# hm3.net
KiCad netlist of a schematic drawn in EAGLE
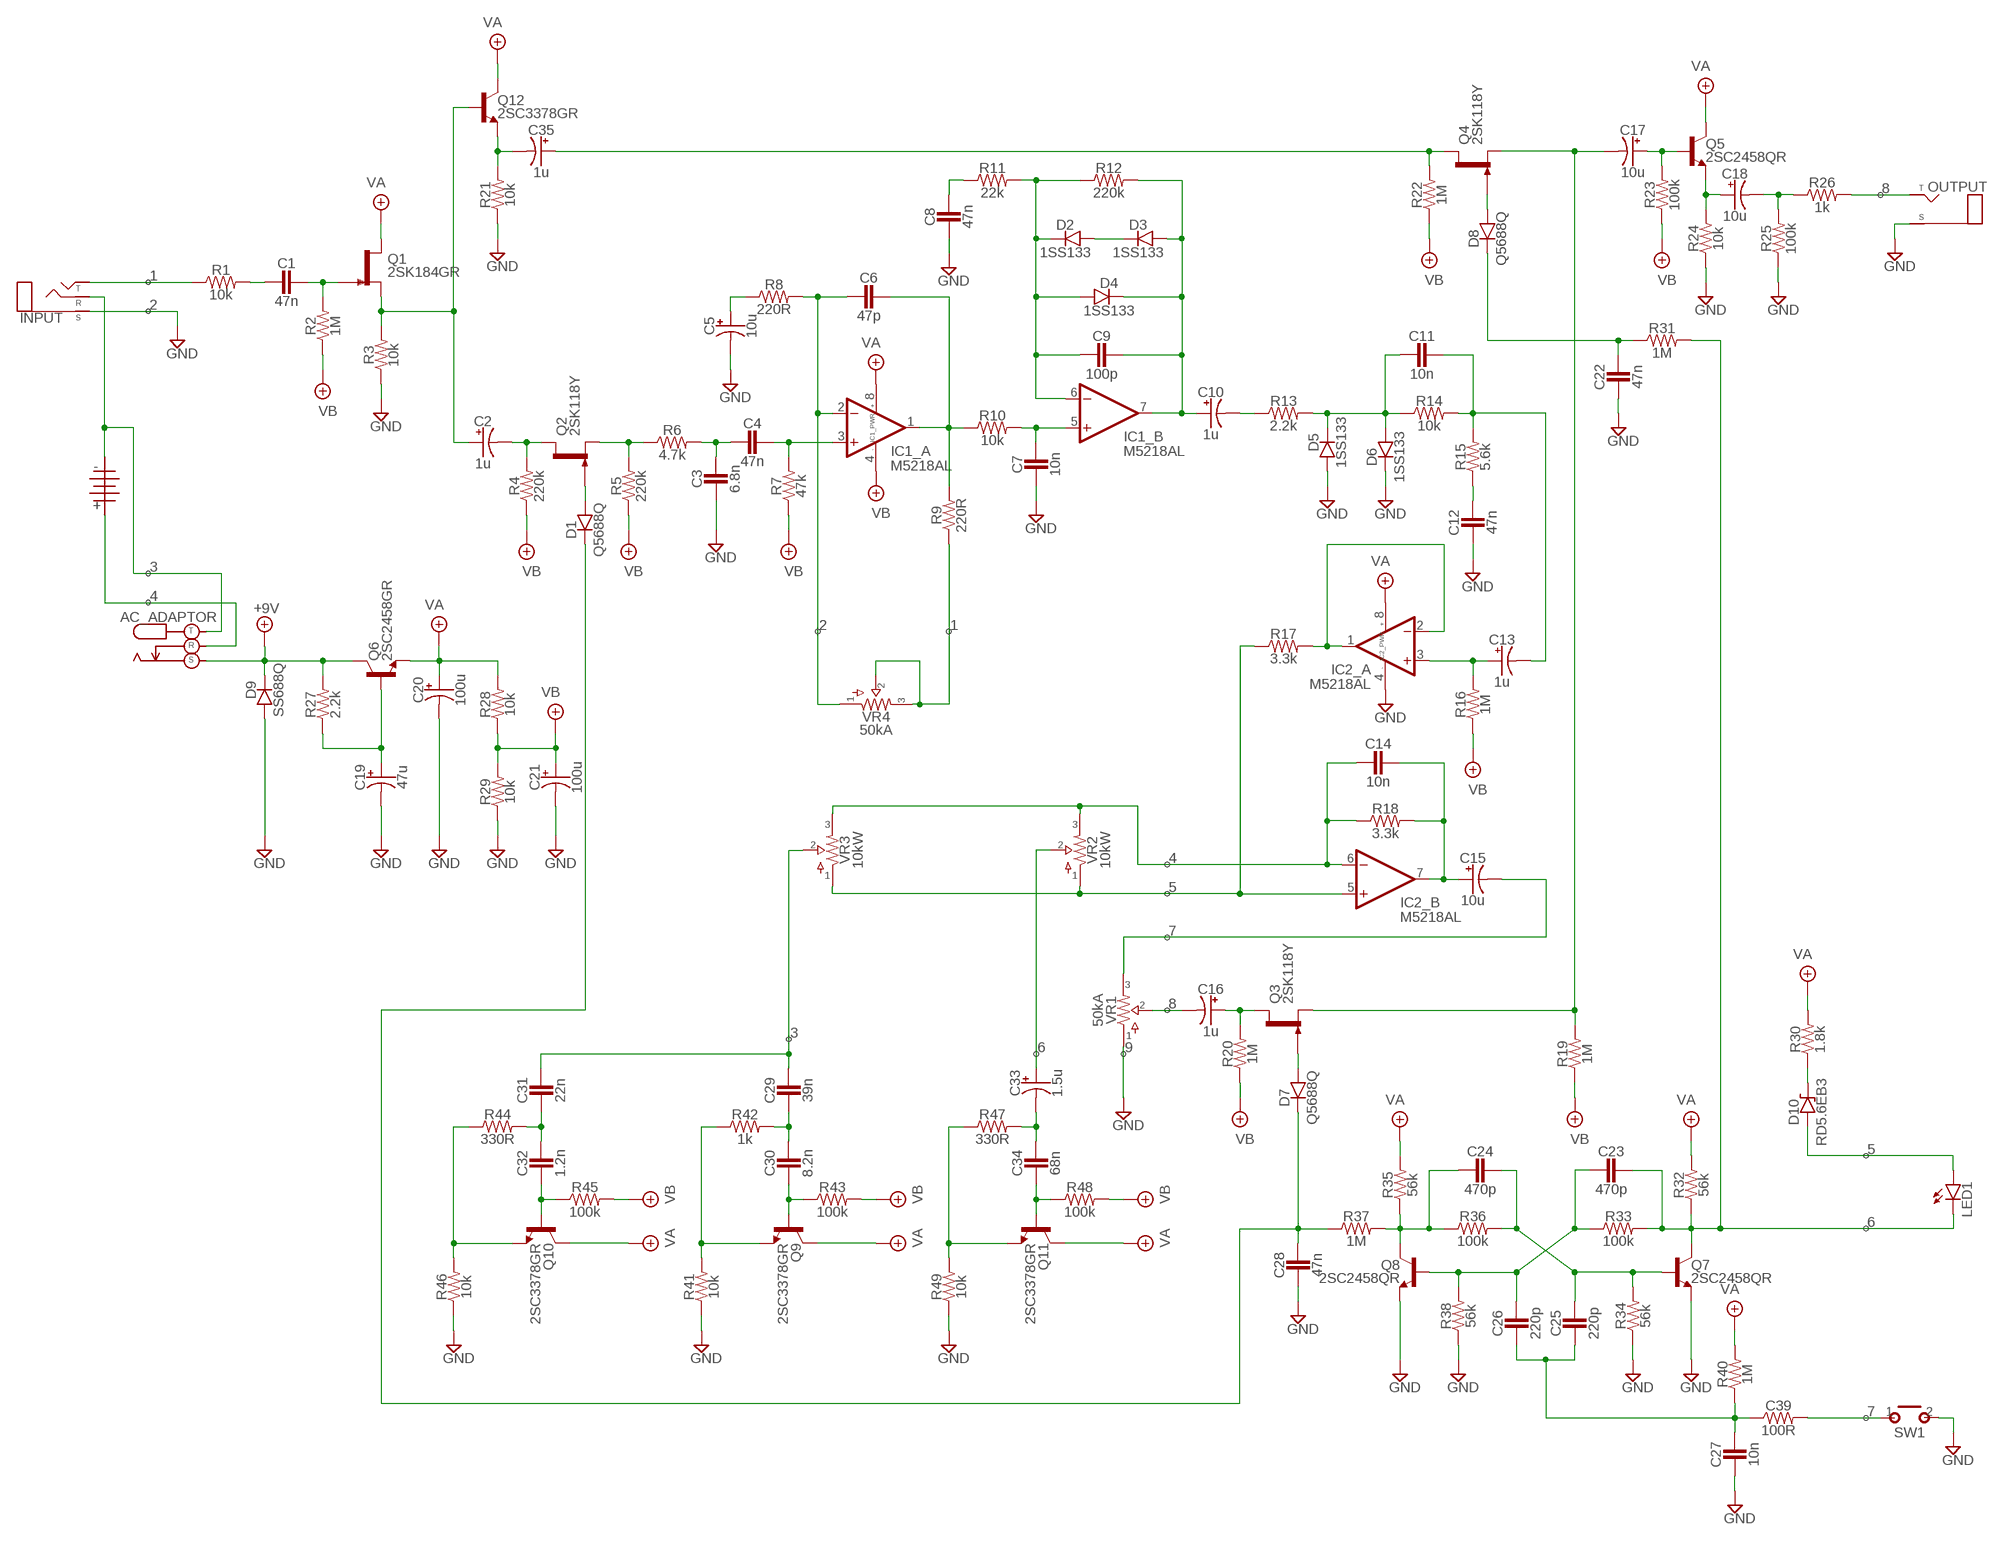
[diagram p0: schematic, sheet 1]

(export (version "E")
  (design (tool "Eeschema 10.0.6"))
  (components
    (comp (ref "1101")
      (value "BATTERY")
      (footprint "eagle-import:TWO_PADS")
      (libsource (lib "eagle-import") (part "BATTERY"))
    )
    (comp (ref "AC_ADAPTOR")
      (value "DC_KOBICONN")
      (footprint "eagle-import:DC_KOBICONN")
      (libsource (lib "eagle-import") (part "DC_KOBICONN"))
    )
    (comp (ref "C1")
      (value "47n")
      (footprint "eagle-import:BOX_SMALL")
      (libsource (lib "eagle-import") (part "CER/FILMBOX.1"))
    )
    (comp (ref "C2")
      (value "1u")
      (footprint "eagle-import:050_020")
      (libsource (lib "eagle-import") (part "0500"))
    )
    (comp (ref "C3")
      (value "6.8n")
      (footprint "eagle-import:BOX_SMALL")
      (libsource (lib "eagle-import") (part "CER/FILMBOX.1"))
    )
    (comp (ref "C4")
      (value "47n")
      (footprint "eagle-import:BOX_SMALL")
      (libsource (lib "eagle-import") (part "CER/FILMBOX.1"))
    )
    (comp (ref "C5")
      (value "10u")
      (footprint "eagle-import:050_020")
      (libsource (lib "eagle-import") (part "0500"))
    )
    (comp (ref "C6")
      (value "47p")
      (footprint "eagle-import:BOX_SMALL")
      (libsource (lib "eagle-import") (part "CER/FILMBOX.1"))
    )
    (comp (ref "C7")
      (value "10n")
      (footprint "eagle-import:BOX_SMALL")
      (libsource (lib "eagle-import") (part "CER/FILMBOX.1"))
    )
    (comp (ref "C8")
      (value "47n")
      (footprint "eagle-import:BOX_SMALL")
      (libsource (lib "eagle-import") (part "CER/FILMBOX.1"))
    )
    (comp (ref "C9")
      (value "100p")
      (footprint "eagle-import:BOX_SMALL")
      (libsource (lib "eagle-import") (part "CER/FILMBOX.1"))
    )
    (comp (ref "C10")
      (value "1u")
      (footprint "eagle-import:050_020")
      (libsource (lib "eagle-import") (part "0500"))
    )
    (comp (ref "C11")
      (value "10n")
      (footprint "eagle-import:BOX_SMALL")
      (libsource (lib "eagle-import") (part "CER/FILMBOX.1"))
    )
    (comp (ref "C12")
      (value "47n")
      (footprint "eagle-import:BOX_SMALL")
      (libsource (lib "eagle-import") (part "CER/FILMBOX.1"))
    )
    (comp (ref "C13")
      (value "1u")
      (footprint "eagle-import:050_020")
      (libsource (lib "eagle-import") (part "0500"))
    )
    (comp (ref "C14")
      (value "10n")
      (footprint "eagle-import:BOX_SMALL")
      (libsource (lib "eagle-import") (part "CER/FILMBOX.1"))
    )
    (comp (ref "C15")
      (value "10u")
      (footprint "eagle-import:050_020")
      (libsource (lib "eagle-import") (part "0500"))
    )
    (comp (ref "C16")
      (value "1u")
      (footprint "eagle-import:050_020")
      (libsource (lib "eagle-import") (part "0500"))
    )
    (comp (ref "C17")
      (value "10u")
      (footprint "eagle-import:050_020")
      (libsource (lib "eagle-import") (part "0500"))
    )
    (comp (ref "C18")
      (value "10u")
      (footprint "eagle-import:050_020")
      (libsource (lib "eagle-import") (part "0500"))
    )
    (comp (ref "C19")
      (value "47u")
      (footprint "eagle-import:050_020")
      (libsource (lib "eagle-import") (part "0500"))
    )
    (comp (ref "C20")
      (value "100u")
      (footprint "eagle-import:050_020")
      (libsource (lib "eagle-import") (part "0500"))
    )
    (comp (ref "C21")
      (value "100u")
      (footprint "eagle-import:050_020")
      (libsource (lib "eagle-import") (part "0500"))
    )
    (comp (ref "C22")
      (value "47n")
      (footprint "eagle-import:BOX_SMALL")
      (libsource (lib "eagle-import") (part "CER/FILMBOX.1"))
    )
    (comp (ref "C23")
      (value "470p")
      (footprint "eagle-import:BOX_SMALL")
      (libsource (lib "eagle-import") (part "CER/FILMBOX.1"))
    )
    (comp (ref "C24")
      (value "470p")
      (footprint "eagle-import:BOX_SMALL")
      (libsource (lib "eagle-import") (part "CER/FILMBOX.1"))
    )
    (comp (ref "C25")
      (value "220p")
      (footprint "eagle-import:BOX_SMALL")
      (libsource (lib "eagle-import") (part "CER/FILMBOX.1"))
    )
    (comp (ref "C26")
      (value "220p")
      (footprint "eagle-import:BOX_SMALL")
      (libsource (lib "eagle-import") (part "CER/FILMBOX.1"))
    )
    (comp (ref "C27")
      (value "10n")
      (footprint "eagle-import:BOX_SMALL")
      (libsource (lib "eagle-import") (part "CER/FILMBOX.1"))
    )
    (comp (ref "C28")
      (value "47n")
      (footprint "eagle-import:BOX_SMALL")
      (libsource (lib "eagle-import") (part "CER/FILMBOX.1"))
    )
    (comp (ref "C29")
      (value "39n")
      (footprint "eagle-import:BOX_SMALL")
      (libsource (lib "eagle-import") (part "CER/FILMBOX.1"))
    )
    (comp (ref "C30")
      (value "8.2n")
      (footprint "eagle-import:BOX_SMALL")
      (libsource (lib "eagle-import") (part "CER/FILMBOX.1"))
    )
    (comp (ref "C31")
      (value "22n")
      (footprint "eagle-import:BOX_SMALL")
      (libsource (lib "eagle-import") (part "CER/FILMBOX.1"))
    )
    (comp (ref "C32")
      (value "1.2n")
      (footprint "eagle-import:BOX_SMALL")
      (libsource (lib "eagle-import") (part "CER/FILMBOX.1"))
    )
    (comp (ref "C33")
      (value "1.5u")
      (footprint "eagle-import:050_020")
      (libsource (lib "eagle-import") (part "0500"))
    )
    (comp (ref "C34")
      (value "68n")
      (footprint "eagle-import:BOX_SMALL")
      (libsource (lib "eagle-import") (part "CER/FILMBOX.1"))
    )
    (comp (ref "C35")
      (value "1u")
      (footprint "eagle-import:050_020")
      (libsource (lib "eagle-import") (part "0500"))
    )
    (comp (ref "C39")
      (value "100R")
      (footprint "eagle-import:R0207_3")
      (libsource (lib "eagle-import") (part "R_.3B"))
    )
    (comp (ref "D1")
      (value "Q5688Q")
      (footprint "eagle-import:DO35-2")
      (libsource (lib "eagle-import") (part "DO35.2"))
    )
    (comp (ref "D2")
      (value "1SS133")
      (footprint "eagle-import:DO35-2")
      (libsource (lib "eagle-import") (part "DO35.2"))
    )
    (comp (ref "D3")
      (value "1SS133")
      (footprint "eagle-import:DO35-2")
      (libsource (lib "eagle-import") (part "DO35.2"))
    )
    (comp (ref "D4")
      (value "1SS133")
      (footprint "eagle-import:DO35-2")
      (libsource (lib "eagle-import") (part "DO35.2"))
    )
    (comp (ref "D5")
      (value "1SS133")
      (footprint "eagle-import:DO35-2")
      (libsource (lib "eagle-import") (part "DO35.2"))
    )
    (comp (ref "D6")
      (value "1SS133")
      (footprint "eagle-import:DO35-2")
      (libsource (lib "eagle-import") (part "DO35.2"))
    )
    (comp (ref "D7")
      (value "Q5688Q")
      (footprint "eagle-import:DO35-2")
      (libsource (lib "eagle-import") (part "DO35.2"))
    )
    (comp (ref "D8")
      (value "Q5688Q")
      (footprint "eagle-import:DO35-2")
      (libsource (lib "eagle-import") (part "DO35.2"))
    )
    (comp (ref "D9")
      (value "SS688Q")
      (footprint "eagle-import:DO35-2")
      (libsource (lib "eagle-import") (part "DO35.2"))
    )
    (comp (ref "D10")
      (value "RD5.6EB3")
      (footprint "eagle-import:DO41-2")
      (libsource (lib "eagle-import") (part "ZENER.2"))
    )
    (comp (ref "IC1")
      (value "M5218AL")
      (footprint "eagle-import:DIL0")
      (libsource (lib "eagle-import") (part "DUALTH"))
    )
    (comp (ref "IC2")
      (value "M5218AL")
      (footprint "eagle-import:SIL08")
      (libsource (lib "eagle-import") (part "DUALSIL"))
    )
    (comp (ref "INPUT")
      (value "STEREO3PADS")
      (footprint "eagle-import:THREEPADS")
      (libsource (lib "eagle-import") (part "STEREO3PADS"))
    )
    (comp (ref "LED1")
      (value "LED")
      (footprint "eagle-import:3MM_D")
      (libsource (lib "eagle-import") (part "LED"))
    )
    (comp (ref "OUTPUT")
      (value "MONO")
      (footprint "eagle-import:TWO_PADS")
      (libsource (lib "eagle-import") (part "MONO"))
    )
    (comp (ref "Q1")
      (value "2SK184GR")
      (footprint "eagle-import:TO92-")
      (libsource (lib "eagle-import") (part "2N5457"))
    )
    (comp (ref "Q2")
      (value "2SK118Y")
      (footprint "eagle-import:TO92-")
      (libsource (lib "eagle-import") (part "2N5457"))
    )
    (comp (ref "Q3")
      (value "2SK118Y")
      (footprint "eagle-import:TO92-")
      (libsource (lib "eagle-import") (part "2N5457"))
    )
    (comp (ref "Q4")
      (value "2SK118Y")
      (footprint "eagle-import:TO92-")
      (libsource (lib "eagle-import") (part "2N5457"))
    )
    (comp (ref "Q5")
      (value "2SC2458QR")
      (footprint "eagle-import:TO92-")
      (libsource (lib "eagle-import") (part "2SC828A"))
    )
    (comp (ref "Q6")
      (value "2SC2458GR")
      (footprint "eagle-import:TO92-")
      (libsource (lib "eagle-import") (part "2SC828A"))
    )
    (comp (ref "Q7")
      (value "2SC2458QR")
      (footprint "eagle-import:TO92-")
      (libsource (lib "eagle-import") (part "2SC828A"))
    )
    (comp (ref "Q8")
      (value "2SC2458QR")
      (footprint "eagle-import:TO92-")
      (libsource (lib "eagle-import") (part "2SC828A"))
    )
    (comp (ref "Q9")
      (value "2SC3378GR")
      (footprint "eagle-import:TO92-")
      (libsource (lib "eagle-import") (part "2SC828A"))
    )
    (comp (ref "Q10")
      (value "2SC3378GR")
      (footprint "eagle-import:TO92-")
      (libsource (lib "eagle-import") (part "2SC828A"))
    )
    (comp (ref "Q11")
      (value "2SC3378GR")
      (footprint "eagle-import:TO92-")
      (libsource (lib "eagle-import") (part "2SC828A"))
    )
    (comp (ref "Q12")
      (value "2SC3378GR")
      (footprint "eagle-import:TO92-")
      (libsource (lib "eagle-import") (part "2SC828A"))
    )
    (comp (ref "R1")
      (value "10k")
      (footprint "eagle-import:R0207_3")
      (libsource (lib "eagle-import") (part "R_.3B"))
    )
    (comp (ref "R2")
      (value "1M")
      (footprint "eagle-import:R0207_3")
      (libsource (lib "eagle-import") (part "R_.3B"))
    )
    (comp (ref "R3")
      (value "10k")
      (footprint "eagle-import:R0207_3")
      (libsource (lib "eagle-import") (part "R_.3B"))
    )
    (comp (ref "R4")
      (value "220k")
      (footprint "eagle-import:R0207_3")
      (libsource (lib "eagle-import") (part "R_.3B"))
    )
    (comp (ref "R5")
      (value "220k")
      (footprint "eagle-import:R0207_3")
      (libsource (lib "eagle-import") (part "R_.3B"))
    )
    (comp (ref "R6")
      (value "4.7k")
      (footprint "eagle-import:R0207_3")
      (libsource (lib "eagle-import") (part "R_.3B"))
    )
    (comp (ref "R7")
      (value "47k")
      (footprint "eagle-import:R0207_3")
      (libsource (lib "eagle-import") (part "R_.3B"))
    )
    (comp (ref "R8")
      (value "220R")
      (footprint "eagle-import:R0207_3")
      (libsource (lib "eagle-import") (part "R_.3B"))
    )
    (comp (ref "R9")
      (value "220R")
      (footprint "eagle-import:R0207_3")
      (libsource (lib "eagle-import") (part "R_.3B"))
    )
    (comp (ref "R10")
      (value "10k")
      (footprint "eagle-import:R0207_3")
      (libsource (lib "eagle-import") (part "R_.3B"))
    )
    (comp (ref "R11")
      (value "22k")
      (footprint "eagle-import:R0207_3")
      (libsource (lib "eagle-import") (part "R_.3B"))
    )
    (comp (ref "R12")
      (value "220k")
      (footprint "eagle-import:R0207_3")
      (libsource (lib "eagle-import") (part "R_.3B"))
    )
    (comp (ref "R13")
      (value "2.2k")
      (footprint "eagle-import:R0207_3")
      (libsource (lib "eagle-import") (part "R_.3B"))
    )
    (comp (ref "R14")
      (value "10k")
      (footprint "eagle-import:R0207_3")
      (libsource (lib "eagle-import") (part "R_.3B"))
    )
    (comp (ref "R15")
      (value "5.6k")
      (footprint "eagle-import:R0207_3")
      (libsource (lib "eagle-import") (part "R_.3B"))
    )
    (comp (ref "R16")
      (value "1M")
      (footprint "eagle-import:R0207_3")
      (libsource (lib "eagle-import") (part "R_.3B"))
    )
    (comp (ref "R17")
      (value "3.3k")
      (footprint "eagle-import:R0207_3")
      (libsource (lib "eagle-import") (part "R_.3B"))
    )
    (comp (ref "R18")
      (value "3.3k")
      (footprint "eagle-import:R0207_3")
      (libsource (lib "eagle-import") (part "R_.3B"))
    )
    (comp (ref "R19")
      (value "1M")
      (footprint "eagle-import:R0207_3")
      (libsource (lib "eagle-import") (part "R_.3B"))
    )
    (comp (ref "R20")
      (value "1M")
      (footprint "eagle-import:R0207_3")
      (libsource (lib "eagle-import") (part "R_.3B"))
    )
    (comp (ref "R21")
      (value "10k")
      (footprint "eagle-import:R0207_3")
      (libsource (lib "eagle-import") (part "R_.3B"))
    )
    (comp (ref "R22")
      (value "1M")
      (footprint "eagle-import:R0207_3")
      (libsource (lib "eagle-import") (part "R_.3B"))
    )
    (comp (ref "R23")
      (value "100k")
      (footprint "eagle-import:R0207_3")
      (libsource (lib "eagle-import") (part "R_.3B"))
    )
    (comp (ref "R24")
      (value "10k")
      (footprint "eagle-import:R0207_3")
      (libsource (lib "eagle-import") (part "R_.3B"))
    )
    (comp (ref "R25")
      (value "100k")
      (footprint "eagle-import:R0207_3")
      (libsource (lib "eagle-import") (part "R_.3B"))
    )
    (comp (ref "R26")
      (value "1k")
      (footprint "eagle-import:R0207_3")
      (libsource (lib "eagle-import") (part "R_.3B"))
    )
    (comp (ref "R27")
      (value "2.2k")
      (footprint "eagle-import:R0207_3")
      (libsource (lib "eagle-import") (part "R_.3B"))
    )
    (comp (ref "R28")
      (value "10k")
      (footprint "eagle-import:R0207_3")
      (libsource (lib "eagle-import") (part "R_.3B"))
    )
    (comp (ref "R29")
      (value "10k")
      (footprint "eagle-import:R0207_3")
      (libsource (lib "eagle-import") (part "R_.3B"))
    )
    (comp (ref "R30")
      (value "1.8k")
      (footprint "eagle-import:R0207_3")
      (libsource (lib "eagle-import") (part "R_.3B"))
    )
    (comp (ref "R31")
      (value "1M")
      (footprint "eagle-import:R0207_3")
      (libsource (lib "eagle-import") (part "R_.3B"))
    )
    (comp (ref "R32")
      (value "56k")
      (footprint "eagle-import:R0207_3")
      (libsource (lib "eagle-import") (part "R_.3B"))
    )
    (comp (ref "R33")
      (value "100k")
      (footprint "eagle-import:R0207_3")
      (libsource (lib "eagle-import") (part "R_.3B"))
    )
    (comp (ref "R34")
      (value "56k")
      (footprint "eagle-import:R0207_3")
      (libsource (lib "eagle-import") (part "R_.3B"))
    )
    (comp (ref "R35")
      (value "56k")
      (footprint "eagle-import:R0207_3")
      (libsource (lib "eagle-import") (part "R_.3B"))
    )
    (comp (ref "R36")
      (value "100k")
      (footprint "eagle-import:R0207_3")
      (libsource (lib "eagle-import") (part "R_.3B"))
    )
    (comp (ref "R37")
      (value "1M")
      (footprint "eagle-import:R0207_3")
      (libsource (lib "eagle-import") (part "R_.3B"))
    )
    (comp (ref "R38")
      (value "56k")
      (footprint "eagle-import:R0207_3")
      (libsource (lib "eagle-import") (part "R_.3B"))
    )
    (comp (ref "R40")
      (value "1M")
      (footprint "eagle-import:R0207_3")
      (libsource (lib "eagle-import") (part "R_.3B"))
    )
    (comp (ref "R41")
      (value "10k")
      (footprint "eagle-import:R0207_3")
      (libsource (lib "eagle-import") (part "R_.3B"))
    )
    (comp (ref "R42")
      (value "1k")
      (footprint "eagle-import:R0207_3")
      (libsource (lib "eagle-import") (part "R_.3B"))
    )
    (comp (ref "R43")
      (value "100k")
      (footprint "eagle-import:R0207_3")
      (libsource (lib "eagle-import") (part "R_.3B"))
    )
    (comp (ref "R44")
      (value "330R")
      (footprint "eagle-import:R0207_3")
      (libsource (lib "eagle-import") (part "R_.3B"))
    )
    (comp (ref "R45")
      (value "100k")
      (footprint "eagle-import:R0207_3")
      (libsource (lib "eagle-import") (part "R_.3B"))
    )
    (comp (ref "R46")
      (value "10k")
      (footprint "eagle-import:R0207_3")
      (libsource (lib "eagle-import") (part "R_.3B"))
    )
    (comp (ref "R47")
      (value "330R")
      (footprint "eagle-import:R0207_3")
      (libsource (lib "eagle-import") (part "R_.3B"))
    )
    (comp (ref "R48")
      (value "100k")
      (footprint "eagle-import:R0207_3")
      (libsource (lib "eagle-import") (part "R_.3B"))
    )
    (comp (ref "R49")
      (value "10k")
      (footprint "eagle-import:R0207_3")
      (libsource (lib "eagle-import") (part "R_.3B"))
    )
    (comp (ref "SW1")
      (value "MOMENTARY")
      (footprint "eagle-import:SPST")
      (libsource (lib "eagle-import") (part "MOMENTARY"))
    )
    (comp (ref "VR1")
      (value "50kA")
      (footprint "eagle-import:16MM")
      (libsource (lib "eagle-import") (part "POTS16MM"))
    )
    (comp (ref "VR2")
      (value "10kW")
      (footprint "eagle-import:16MM")
      (libsource (lib "eagle-import") (part "POTS16MM"))
    )
    (comp (ref "VR3")
      (value "10kW")
      (footprint "eagle-import:16MM")
      (libsource (lib "eagle-import") (part "POTS16MM"))
    )
    (comp (ref "VR4")
      (value "50kA")
      (footprint "eagle-import:16MM")
      (libsource (lib "eagle-import") (part "POTS16MM"))
    )
  )
  (nets
    (net (code "1") (name "+9V") (class "Default")
      (node (ref "AC_ADAPTOR") (pin "S") (pinfunction "S_S") (pintype "bidirectional"))
      (node (ref "D9") (pin "C") (pinfunction "C_C") (pintype "passive"))
      (node (ref "Q6") (pin "2") (pinfunction "C_2") (pintype "passive"))
      (node (ref "R27") (pin "2") (pinfunction "2_2") (pintype "passive"))
    )
    (net (code "2") (name "GND") (class "Default")
      (node (ref "C12") (pin "2") (pinfunction "2_2") (pintype "passive"))
      (node (ref "C19") (pin "-") (pinfunction "-_-") (pintype "passive"))
      (node (ref "C20") (pin "-") (pinfunction "-_-") (pintype "passive"))
      (node (ref "C21") (pin "-") (pinfunction "-_-") (pintype "passive"))
      (node (ref "C22") (pin "2") (pinfunction "2_2") (pintype "passive"))
      (node (ref "C27") (pin "2") (pinfunction "2_2") (pintype "passive"))
      (node (ref "C28") (pin "2") (pinfunction "2_2") (pintype "passive"))
      (node (ref "C3") (pin "2") (pinfunction "2_2") (pintype "passive"))
      (node (ref "C5") (pin "-") (pinfunction "-_-") (pintype "passive"))
      (node (ref "C7") (pin "2") (pinfunction "2_2") (pintype "passive"))
      (node (ref "C8") (pin "2") (pinfunction "2_2") (pintype "passive"))
      (node (ref "D5") (pin "A") (pinfunction "A_A") (pintype "passive"))
      (node (ref "D6") (pin "C") (pinfunction "C_C") (pintype "passive"))
      (node (ref "D9") (pin "A") (pinfunction "A_A") (pintype "passive"))
      (node (ref "IC2") (pin "4") (pinfunction "V-_4") (pintype "power_in"))
      (node (ref "INPUT") (pin "SLEEVE") (pinfunction "S_SLEEVE") (pintype "passive"))
      (node (ref "OUTPUT") (pin "S") (pinfunction "SLEEVE_S") (pintype "passive"))
      (node (ref "Q7") (pin "3") (pinfunction "E_3") (pintype "passive"))
      (node (ref "Q8") (pin "3") (pinfunction "E_3") (pintype "passive"))
      (node (ref "R21") (pin "1") (pinfunction "1_1") (pintype "passive"))
      (node (ref "R24") (pin "1") (pinfunction "1_1") (pintype "passive"))
      (node (ref "R25") (pin "1") (pinfunction "1_1") (pintype "passive"))
      (node (ref "R29") (pin "1") (pinfunction "1_1") (pintype "passive"))
      (node (ref "R3") (pin "1") (pinfunction "1_1") (pintype "passive"))
      (node (ref "R34") (pin "1") (pinfunction "1_1") (pintype "passive"))
      (node (ref "R38") (pin "1") (pinfunction "1_1") (pintype "passive"))
      (node (ref "R41") (pin "1") (pinfunction "1_1") (pintype "passive"))
      (node (ref "R46") (pin "1") (pinfunction "1_1") (pintype "passive"))
      (node (ref "R49") (pin "1") (pinfunction "1_1") (pintype "passive"))
      (node (ref "SW1") (pin "2") (pinfunction "S_2") (pintype "passive"))
      (node (ref "VR1") (pin "1") (pinfunction "1_1") (pintype "passive"))
    )
    (net (code "3") (name "Net-(1101-P$1)") (class "Default")
      (node (ref "1101") (pin "T") (pinfunction "P$1_T") (pintype "bidirectional"))
      (node (ref "AC_ADAPTOR") (pin "R") (pinfunction "R_R") (pintype "bidirectional"))
    )
    (net (code "4") (name "Net-(1101-P$2)") (class "Default")
      (node (ref "1101") (pin "S") (pinfunction "P$2_S") (pintype "bidirectional"))
      (node (ref "AC_ADAPTOR") (pin "T") (pinfunction "T_T") (pintype "bidirectional"))
      (node (ref "INPUT") (pin "RING") (pinfunction "R_RING") (pintype "passive"))
    )
    (net (code "5") (name "Net-(C1-Pad2)") (class "Default")
      (node (ref "C1") (pin "2") (pinfunction "2_2") (pintype "passive"))
      (node (ref "R1") (pin "2") (pinfunction "2_2") (pintype "passive"))
    )
    (net (code "6") (name "Net-(C3-Pad1)") (class "Default")
      (node (ref "C3") (pin "1") (pinfunction "1_1") (pintype "passive"))
      (node (ref "C4") (pin "2") (pinfunction "2_2") (pintype "passive"))
      (node (ref "R6") (pin "2") (pinfunction "2_2") (pintype "passive"))
    )
    (net (code "7") (name "Net-(C5-Pad+)") (class "Default")
      (node (ref "C5") (pin "+") (pinfunction "+_+") (pintype "passive"))
      (node (ref "R8") (pin "1") (pinfunction "1_1") (pintype "passive"))
    )
    (net (code "8") (name "Net-(C8-Pad1)") (class "Default")
      (node (ref "C8") (pin "1") (pinfunction "1_1") (pintype "passive"))
      (node (ref "R11") (pin "1") (pinfunction "1_1") (pintype "passive"))
    )
    (net (code "9") (name "Net-(C10-Pad-)") (class "Default")
      (node (ref "C10") (pin "-") (pinfunction "-_-") (pintype "passive"))
      (node (ref "R13") (pin "1") (pinfunction "1_1") (pintype "passive"))
    )
    (net (code "10") (name "Net-(C11-Pad1)") (class "Default")
      (node (ref "C11") (pin "1") (pinfunction "1_1") (pintype "passive"))
      (node (ref "C13") (pin "-") (pinfunction "-_-") (pintype "passive"))
      (node (ref "R14") (pin "2") (pinfunction "2_2") (pintype "passive"))
      (node (ref "R15") (pin "2") (pinfunction "2_2") (pintype "passive"))
    )
    (net (code "11") (name "Net-(C11-Pad2)") (class "Default")
      (node (ref "C11") (pin "2") (pinfunction "2_2") (pintype "passive"))
      (node (ref "D5") (pin "C") (pinfunction "C_C") (pintype "passive"))
      (node (ref "D6") (pin "A") (pinfunction "A_A") (pintype "passive"))
      (node (ref "R13") (pin "2") (pinfunction "2_2") (pintype "passive"))
      (node (ref "R14") (pin "1") (pinfunction "1_1") (pintype "passive"))
    )
    (net (code "12") (name "Net-(C12-Pad1)") (class "Default")
      (node (ref "C12") (pin "1") (pinfunction "1_1") (pintype "passive"))
      (node (ref "R15") (pin "1") (pinfunction "1_1") (pintype "passive"))
    )
    (net (code "13") (name "Net-(C15-Pad-)") (class "Default")
      (node (ref "C15") (pin "-") (pinfunction "-_-") (pintype "passive"))
      (node (ref "VR1") (pin "3") (pinfunction "3_3") (pintype "passive"))
    )
    (net (code "14") (name "Net-(C16-Pad-)") (class "Default")
      (node (ref "C16") (pin "-") (pinfunction "-_-") (pintype "passive"))
      (node (ref "VR1") (pin "2") (pinfunction "2_2") (pintype "passive"))
    )
    (net (code "15") (name "Net-(C18-Pad-)") (class "Default")
      (node (ref "C18") (pin "-") (pinfunction "-_-") (pintype "passive"))
      (node (ref "R25") (pin "2") (pinfunction "2_2") (pintype "passive"))
      (node (ref "R26") (pin "1") (pinfunction "1_1") (pintype "passive"))
    )
    (net (code "16") (name "Net-(C22-Pad1)") (class "Default")
      (node (ref "C22") (pin "1") (pinfunction "1_1") (pintype "passive"))
      (node (ref "D8") (pin "C") (pinfunction "C_C") (pintype "passive"))
      (node (ref "R31") (pin "1") (pinfunction "1_1") (pintype "passive"))
    )
    (net (code "17") (name "Net-(C25-Pad2)") (class "Default")
      (node (ref "C25") (pin "2") (pinfunction "2_2") (pintype "passive"))
      (node (ref "C26") (pin "2") (pinfunction "2_2") (pintype "passive"))
      (node (ref "C27") (pin "1") (pinfunction "1_1") (pintype "passive"))
      (node (ref "C39") (pin "1") (pinfunction "1_1") (pintype "passive"))
      (node (ref "R40") (pin "1") (pinfunction "1_1") (pintype "passive"))
    )
    (net (code "18") (name "Net-(C28-Pad1)") (class "Default")
      (node (ref "C28") (pin "1") (pinfunction "1_1") (pintype "passive"))
      (node (ref "D1") (pin "C") (pinfunction "C_C") (pintype "passive"))
      (node (ref "D7") (pin "C") (pinfunction "C_C") (pintype "passive"))
      (node (ref "R37") (pin "1") (pinfunction "1_1") (pintype "passive"))
    )
    (net (code "19") (name "Net-(C29-Pad1)") (class "Default")
      (node (ref "C29") (pin "1") (pinfunction "1_1") (pintype "passive"))
      (node (ref "C31") (pin "1") (pinfunction "1_1") (pintype "passive"))
      (node (ref "VR3") (pin "2") (pinfunction "2_2") (pintype "passive"))
    )
    (net (code "20") (name "Net-(C29-Pad2)") (class "Default")
      (node (ref "C29") (pin "2") (pinfunction "2_2") (pintype "passive"))
      (node (ref "C30") (pin "1") (pinfunction "1_1") (pintype "passive"))
      (node (ref "R42") (pin "2") (pinfunction "2_2") (pintype "passive"))
    )
    (net (code "21") (name "Net-(C31-Pad2)") (class "Default")
      (node (ref "C31") (pin "2") (pinfunction "2_2") (pintype "passive"))
      (node (ref "C32") (pin "1") (pinfunction "1_1") (pintype "passive"))
      (node (ref "R44") (pin "2") (pinfunction "2_2") (pintype "passive"))
    )
    (net (code "22") (name "Net-(C33-Pad+)") (class "Default")
      (node (ref "C33") (pin "+") (pinfunction "+_+") (pintype "passive"))
      (node (ref "VR2") (pin "2") (pinfunction "2_2") (pintype "passive"))
    )
    (net (code "23") (name "Net-(C33-Pad-)") (class "Default")
      (node (ref "C33") (pin "-") (pinfunction "-_-") (pintype "passive"))
      (node (ref "C34") (pin "1") (pinfunction "1_1") (pintype "passive"))
      (node (ref "R47") (pin "2") (pinfunction "2_2") (pintype "passive"))
    )
    (net (code "24") (name "Net-(D2-PadA)") (class "Default")
      (node (ref "D2") (pin "A") (pinfunction "A_A") (pintype "passive"))
      (node (ref "D3") (pin "C") (pinfunction "C_C") (pintype "passive"))
    )
    (net (code "25") (name "Net-(D10-PadC)") (class "Default")
      (node (ref "D10") (pin "C") (pinfunction "C_C") (pintype "passive"))
      (node (ref "R30") (pin "1") (pinfunction "1_1") (pintype "passive"))
    )
    (net (code "26") (name "Net-(IC1A-+IN)") (class "Default")
      (node (ref "C4") (pin "1") (pinfunction "1_1") (pintype "passive"))
      (node (ref "IC1") (pin "3") (pinfunction "+IN_3") (pintype "input"))
      (node (ref "R7") (pin "2") (pinfunction "2_2") (pintype "passive"))
    )
    (net (code "27") (name "Net-(IC1A--IN)") (class "Default")
      (node (ref "C6") (pin "2") (pinfunction "2_2") (pintype "passive"))
      (node (ref "IC1") (pin "2") (pinfunction "-IN_2") (pintype "input"))
      (node (ref "R8") (pin "2") (pinfunction "2_2") (pintype "passive"))
      (node (ref "VR4") (pin "1") (pinfunction "1_1") (pintype "passive"))
    )
    (net (code "28") (name "Net-(IC1A-OUT)") (class "Default")
      (node (ref "C6") (pin "1") (pinfunction "1_1") (pintype "passive"))
      (node (ref "IC1") (pin "1") (pinfunction "OUT_1") (pintype "output"))
      (node (ref "R10") (pin "1") (pinfunction "1_1") (pintype "passive"))
      (node (ref "R9") (pin "2") (pinfunction "2_2") (pintype "passive"))
    )
    (net (code "29") (name "Net-(IC1B-+IN)") (class "Default")
      (node (ref "C7") (pin "1") (pinfunction "1_1") (pintype "passive"))
      (node (ref "IC1") (pin "5") (pinfunction "+IN_5") (pintype "input"))
      (node (ref "R10") (pin "2") (pinfunction "2_2") (pintype "passive"))
    )
    (net (code "30") (name "Net-(IC1B--IN)") (class "Default")
      (node (ref "C9") (pin "2") (pinfunction "2_2") (pintype "passive"))
      (node (ref "D2") (pin "C") (pinfunction "C_C") (pintype "passive"))
      (node (ref "D4") (pin "A") (pinfunction "A_A") (pintype "passive"))
      (node (ref "IC1") (pin "6") (pinfunction "-IN_6") (pintype "input"))
      (node (ref "R11") (pin "2") (pinfunction "2_2") (pintype "passive"))
      (node (ref "R12") (pin "1") (pinfunction "1_1") (pintype "passive"))
    )
    (net (code "31") (name "Net-(IC1B-OUT)") (class "Default")
      (node (ref "C10") (pin "+") (pinfunction "+_+") (pintype "passive"))
      (node (ref "C9") (pin "1") (pinfunction "1_1") (pintype "passive"))
      (node (ref "D3") (pin "A") (pinfunction "A_A") (pintype "passive"))
      (node (ref "D4") (pin "C") (pinfunction "C_C") (pintype "passive"))
      (node (ref "IC1") (pin "7") (pinfunction "OUT_7") (pintype "output"))
      (node (ref "R12") (pin "2") (pinfunction "2_2") (pintype "passive"))
    )
    (net (code "32") (name "Net-(IC2A-+IN)") (class "Default")
      (node (ref "C13") (pin "+") (pinfunction "+_+") (pintype "passive"))
      (node (ref "IC2") (pin "3") (pinfunction "+IN_3") (pintype "input"))
      (node (ref "R16") (pin "2") (pinfunction "2_2") (pintype "passive"))
    )
    (net (code "33") (name "Net-(IC2A--IN)") (class "Default")
      (node (ref "IC2") (pin "1") (pinfunction "OUT_1") (pintype "output"))
      (node (ref "IC2") (pin "2") (pinfunction "-IN_2") (pintype "input"))
      (node (ref "R17") (pin "2") (pinfunction "2_2") (pintype "passive"))
    )
    (net (code "34") (name "Net-(IC2B-+IN)") (class "Default")
      (node (ref "IC2") (pin "5") (pinfunction "+IN_5") (pintype "input"))
      (node (ref "R17") (pin "1") (pinfunction "1_1") (pintype "passive"))
      (node (ref "VR2") (pin "1") (pinfunction "1_1") (pintype "passive"))
      (node (ref "VR3") (pin "1") (pinfunction "1_1") (pintype "passive"))
    )
    (net (code "35") (name "Net-(IC2B--IN)") (class "Default")
      (node (ref "C14") (pin "2") (pinfunction "2_2") (pintype "passive"))
      (node (ref "IC2") (pin "6") (pinfunction "-IN_6") (pintype "input"))
      (node (ref "R18") (pin "1") (pinfunction "1_1") (pintype "passive"))
      (node (ref "VR2") (pin "3") (pinfunction "3_3") (pintype "passive"))
      (node (ref "VR3") (pin "3") (pinfunction "3_3") (pintype "passive"))
    )
    (net (code "36") (name "Net-(IC2B-OUT)") (class "Default")
      (node (ref "C14") (pin "1") (pinfunction "1_1") (pintype "passive"))
      (node (ref "C15") (pin "+") (pinfunction "+_+") (pintype "passive"))
      (node (ref "IC2") (pin "7") (pinfunction "OUT_7") (pintype "output"))
      (node (ref "R18") (pin "2") (pinfunction "2_2") (pintype "passive"))
    )
    (net (code "37") (name "Net-(INPUT-T)") (class "Default")
      (node (ref "INPUT") (pin "TIP") (pinfunction "T_TIP") (pintype "passive"))
      (node (ref "R1") (pin "1") (pinfunction "1_1") (pintype "passive"))
    )
    (net (code "38") (name "Net-(LED1-A)") (class "Default")
      (node (ref "D10") (pin "A") (pinfunction "A_A") (pintype "passive"))
      (node (ref "LED1") (pin "ANODE") (pinfunction "A_ANODE") (pintype "passive"))
    )
    (net (code "39") (name "Net-(LED1-C)") (class "Default")
      (node (ref "C23") (pin "1") (pinfunction "1_1") (pintype "passive"))
      (node (ref "LED1") (pin "P$1") (pinfunction "C_P$1") (pintype "passive"))
      (node (ref "Q7") (pin "2") (pinfunction "C_2") (pintype "passive"))
      (node (ref "R31") (pin "2") (pinfunction "2_2") (pintype "passive"))
      (node (ref "R32") (pin "1") (pinfunction "1_1") (pintype "passive"))
      (node (ref "R33") (pin "2") (pinfunction "2_2") (pintype "passive"))
    )
    (net (code "40") (name "Net-(OUTPUT-TIP)") (class "Default")
      (node (ref "OUTPUT") (pin "T") (pinfunction "TIP_T") (pintype "passive"))
      (node (ref "R26") (pin "2") (pinfunction "2_2") (pintype "passive"))
    )
    (net (code "41") (name "Net-(Q1-G)") (class "Default")
      (node (ref "C1") (pin "1") (pinfunction "1_1") (pintype "passive"))
      (node (ref "Q1") (pin "1") (pinfunction "G_1") (pintype "passive"))
      (node (ref "R2") (pin "2") (pinfunction "2_2") (pintype "passive"))
    )
    (net (code "42") (name "Net-(Q1-S)") (class "Default")
      (node (ref "C2") (pin "+") (pinfunction "+_+") (pintype "passive"))
      (node (ref "Q1") (pin "2") (pinfunction "S_2") (pintype "passive"))
      (node (ref "Q12") (pin "1") (pinfunction "B_1") (pintype "passive"))
      (node (ref "R3") (pin "2") (pinfunction "2_2") (pintype "passive"))
    )
    (net (code "43") (name "Net-(Q2-D)") (class "Default")
      (node (ref "C2") (pin "-") (pinfunction "-_-") (pintype "passive"))
      (node (ref "Q2") (pin "3") (pinfunction "D_3") (pintype "passive"))
      (node (ref "R4") (pin "2") (pinfunction "2_2") (pintype "passive"))
    )
    (net (code "44") (name "Net-(Q2-G)") (class "Default")
      (node (ref "D1") (pin "A") (pinfunction "A_A") (pintype "passive"))
      (node (ref "Q2") (pin "1") (pinfunction "G_1") (pintype "passive"))
    )
    (net (code "45") (name "Net-(Q2-S)") (class "Default")
      (node (ref "Q2") (pin "2") (pinfunction "S_2") (pintype "passive"))
      (node (ref "R5") (pin "2") (pinfunction "2_2") (pintype "passive"))
      (node (ref "R6") (pin "1") (pinfunction "1_1") (pintype "passive"))
    )
    (net (code "46") (name "Net-(Q3-D)") (class "Default")
      (node (ref "C16") (pin "+") (pinfunction "+_+") (pintype "passive"))
      (node (ref "Q3") (pin "3") (pinfunction "D_3") (pintype "passive"))
      (node (ref "R20") (pin "2") (pinfunction "2_2") (pintype "passive"))
    )
    (net (code "47") (name "Net-(Q3-G)") (class "Default")
      (node (ref "D7") (pin "A") (pinfunction "A_A") (pintype "passive"))
      (node (ref "Q3") (pin "1") (pinfunction "G_1") (pintype "passive"))
    )
    (net (code "48") (name "Net-(Q3-S)") (class "Default")
      (node (ref "C17") (pin "-") (pinfunction "-_-") (pintype "passive"))
      (node (ref "Q3") (pin "2") (pinfunction "S_2") (pintype "passive"))
      (node (ref "Q4") (pin "2") (pinfunction "S_2") (pintype "passive"))
      (node (ref "R19") (pin "2") (pinfunction "2_2") (pintype "passive"))
    )
    (net (code "49") (name "Net-(Q4-D)") (class "Default")
      (node (ref "C35") (pin "+") (pinfunction "+_+") (pintype "passive"))
      (node (ref "Q4") (pin "3") (pinfunction "D_3") (pintype "passive"))
      (node (ref "R22") (pin "2") (pinfunction "2_2") (pintype "passive"))
    )
    (net (code "50") (name "Net-(Q4-G)") (class "Default")
      (node (ref "D8") (pin "A") (pinfunction "A_A") (pintype "passive"))
      (node (ref "Q4") (pin "1") (pinfunction "G_1") (pintype "passive"))
    )
    (net (code "51") (name "Net-(Q5-B)") (class "Default")
      (node (ref "C17") (pin "+") (pinfunction "+_+") (pintype "passive"))
      (node (ref "Q5") (pin "1") (pinfunction "B_1") (pintype "passive"))
      (node (ref "R23") (pin "2") (pinfunction "2_2") (pintype "passive"))
    )
    (net (code "52") (name "Net-(Q5-E)") (class "Default")
      (node (ref "C18") (pin "+") (pinfunction "+_+") (pintype "passive"))
      (node (ref "Q5") (pin "3") (pinfunction "E_3") (pintype "passive"))
      (node (ref "R24") (pin "2") (pinfunction "2_2") (pintype "passive"))
    )
    (net (code "53") (name "Net-(Q6-B)") (class "Default")
      (node (ref "C19") (pin "+") (pinfunction "+_+") (pintype "passive"))
      (node (ref "Q6") (pin "1") (pinfunction "B_1") (pintype "passive"))
      (node (ref "R27") (pin "1") (pinfunction "1_1") (pintype "passive"))
    )
    (net (code "54") (name "Net-(Q7-B)") (class "Default")
      (node (ref "C24") (pin "1") (pinfunction "1_1") (pintype "passive"))
      (node (ref "C25") (pin "1") (pinfunction "1_1") (pintype "passive"))
      (node (ref "Q7") (pin "1") (pinfunction "B_1") (pintype "passive"))
      (node (ref "R34") (pin "2") (pinfunction "2_2") (pintype "passive"))
      (node (ref "R36") (pin "2") (pinfunction "2_2") (pintype "passive"))
    )
    (net (code "55") (name "Net-(Q8-B)") (class "Default")
      (node (ref "C23") (pin "2") (pinfunction "2_2") (pintype "passive"))
      (node (ref "C26") (pin "1") (pinfunction "1_1") (pintype "passive"))
      (node (ref "Q8") (pin "1") (pinfunction "B_1") (pintype "passive"))
      (node (ref "R33") (pin "1") (pinfunction "1_1") (pintype "passive"))
      (node (ref "R38") (pin "2") (pinfunction "2_2") (pintype "passive"))
    )
    (net (code "56") (name "Net-(Q8-C)") (class "Default")
      (node (ref "C24") (pin "2") (pinfunction "2_2") (pintype "passive"))
      (node (ref "Q8") (pin "2") (pinfunction "C_2") (pintype "passive"))
      (node (ref "R35") (pin "1") (pinfunction "1_1") (pintype "passive"))
      (node (ref "R36") (pin "1") (pinfunction "1_1") (pintype "passive"))
      (node (ref "R37") (pin "2") (pinfunction "2_2") (pintype "passive"))
    )
    (net (code "57") (name "Net-(Q9-B)") (class "Default")
      (node (ref "C30") (pin "2") (pinfunction "2_2") (pintype "passive"))
      (node (ref "Q9") (pin "1") (pinfunction "B_1") (pintype "passive"))
      (node (ref "R43") (pin "1") (pinfunction "1_1") (pintype "passive"))
    )
    (net (code "58") (name "Net-(Q9-E)") (class "Default")
      (node (ref "Q9") (pin "3") (pinfunction "E_3") (pintype "passive"))
      (node (ref "R41") (pin "2") (pinfunction "2_2") (pintype "passive"))
      (node (ref "R42") (pin "1") (pinfunction "1_1") (pintype "passive"))
    )
    (net (code "59") (name "Net-(Q10-B)") (class "Default")
      (node (ref "C32") (pin "2") (pinfunction "2_2") (pintype "passive"))
      (node (ref "Q10") (pin "1") (pinfunction "B_1") (pintype "passive"))
      (node (ref "R45") (pin "1") (pinfunction "1_1") (pintype "passive"))
    )
    (net (code "60") (name "Net-(Q10-E)") (class "Default")
      (node (ref "Q10") (pin "3") (pinfunction "E_3") (pintype "passive"))
      (node (ref "R44") (pin "1") (pinfunction "1_1") (pintype "passive"))
      (node (ref "R46") (pin "2") (pinfunction "2_2") (pintype "passive"))
    )
    (net (code "61") (name "Net-(Q11-B)") (class "Default")
      (node (ref "C34") (pin "2") (pinfunction "2_2") (pintype "passive"))
      (node (ref "Q11") (pin "1") (pinfunction "B_1") (pintype "passive"))
      (node (ref "R48") (pin "1") (pinfunction "1_1") (pintype "passive"))
    )
    (net (code "62") (name "Net-(Q11-E)") (class "Default")
      (node (ref "Q11") (pin "3") (pinfunction "E_3") (pintype "passive"))
      (node (ref "R47") (pin "1") (pinfunction "1_1") (pintype "passive"))
      (node (ref "R49") (pin "2") (pinfunction "2_2") (pintype "passive"))
    )
    (net (code "63") (name "Net-(Q12-E)") (class "Default")
      (node (ref "C35") (pin "-") (pinfunction "-_-") (pintype "passive"))
      (node (ref "Q12") (pin "3") (pinfunction "E_3") (pintype "passive"))
      (node (ref "R21") (pin "2") (pinfunction "2_2") (pintype "passive"))
    )
    (net (code "64") (name "Net-(R9-Pad1)") (class "Default")
      (node (ref "R9") (pin "1") (pinfunction "1_1") (pintype "passive"))
      (node (ref "VR4") (pin "2") (pinfunction "2_2") (pintype "passive"))
      (node (ref "VR4") (pin "3") (pinfunction "3_3") (pintype "passive"))
    )
    (net (code "65") (name "Net-(SW1-P)") (class "Default")
      (node (ref "C39") (pin "2") (pinfunction "2_2") (pintype "passive"))
      (node (ref "SW1") (pin "1") (pinfunction "P_1") (pintype "passive"))
    )
    (net (code "66") (name "VA") (class "Default")
      (node (ref "C20") (pin "+") (pinfunction "+_+") (pintype "passive"))
      (node (ref "IC1") (pin "8") (pinfunction "V+_8") (pintype "power_in"))
      (node (ref "IC2") (pin "8") (pinfunction "V+_8") (pintype "power_in"))
      (node (ref "Q1") (pin "3") (pinfunction "D_3") (pintype "passive"))
      (node (ref "Q10") (pin "2") (pinfunction "C_2") (pintype "passive"))
      (node (ref "Q11") (pin "2") (pinfunction "C_2") (pintype "passive"))
      (node (ref "Q12") (pin "2") (pinfunction "C_2") (pintype "passive"))
      (node (ref "Q5") (pin "2") (pinfunction "C_2") (pintype "passive"))
      (node (ref "Q6") (pin "3") (pinfunction "E_3") (pintype "passive"))
      (node (ref "Q9") (pin "2") (pinfunction "C_2") (pintype "passive"))
      (node (ref "R28") (pin "2") (pinfunction "2_2") (pintype "passive"))
      (node (ref "R30") (pin "2") (pinfunction "2_2") (pintype "passive"))
      (node (ref "R32") (pin "2") (pinfunction "2_2") (pintype "passive"))
      (node (ref "R35") (pin "2") (pinfunction "2_2") (pintype "passive"))
      (node (ref "R40") (pin "2") (pinfunction "2_2") (pintype "passive"))
    )
    (net (code "67") (name "VB") (class "Default")
      (node (ref "C21") (pin "+") (pinfunction "+_+") (pintype "passive"))
      (node (ref "IC1") (pin "4") (pinfunction "V-_4") (pintype "power_in"))
      (node (ref "R16") (pin "1") (pinfunction "1_1") (pintype "passive"))
      (node (ref "R19") (pin "1") (pinfunction "1_1") (pintype "passive"))
      (node (ref "R2") (pin "1") (pinfunction "1_1") (pintype "passive"))
      (node (ref "R20") (pin "1") (pinfunction "1_1") (pintype "passive"))
      (node (ref "R22") (pin "1") (pinfunction "1_1") (pintype "passive"))
      (node (ref "R23") (pin "1") (pinfunction "1_1") (pintype "passive"))
      (node (ref "R28") (pin "1") (pinfunction "1_1") (pintype "passive"))
      (node (ref "R29") (pin "2") (pinfunction "2_2") (pintype "passive"))
      (node (ref "R4") (pin "1") (pinfunction "1_1") (pintype "passive"))
      (node (ref "R43") (pin "2") (pinfunction "2_2") (pintype "passive"))
      (node (ref "R45") (pin "2") (pinfunction "2_2") (pintype "passive"))
      (node (ref "R48") (pin "2") (pinfunction "2_2") (pintype "passive"))
      (node (ref "R5") (pin "1") (pinfunction "1_1") (pintype "passive"))
      (node (ref "R7") (pin "1") (pinfunction "1_1") (pintype "passive"))
    )
  )
)
